# S3C_FrontpanelInterface.net
KiCad netlist of a schematic drawn in Altium Designer
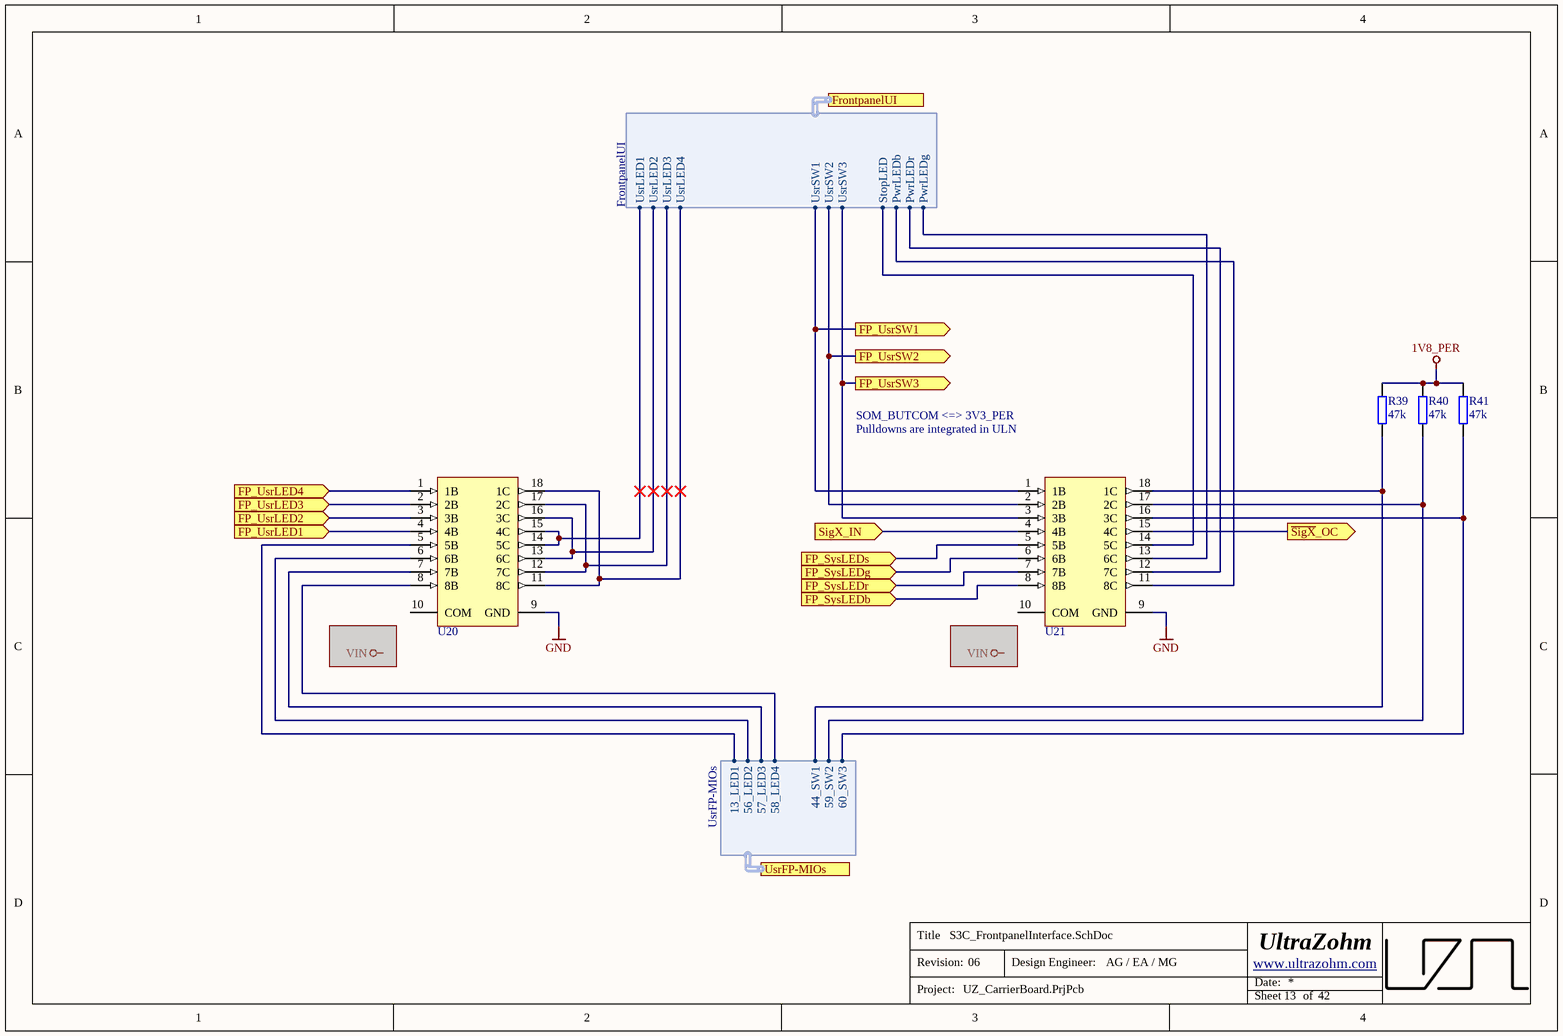
[diagram p0: S3C_FrontpanelInterface.SchDoc]

(export (version "E")
  (design (tool "Eeschema 10.0.6"))
  (components
    (comp (ref "R39")
      (value "47k")
      (footprint "R_0603_TE")
      (description "Generic resistor")
      (fields
        (field (name "MANUFACTURER PART NUMBER") "UZgen_R_0603_47k")
        (field (name "MANUFACTURER") "UZgen")
        (field (name "CREATED FROM") "UZgenTool")
      )
      (libsource (lib "user") (part "RES"))
    )
    (comp (ref "R40")
      (value "47k")
      (footprint "R_0603_TE")
      (description "Generic resistor")
      (fields
        (field (name "MANUFACTURER PART NUMBER") "UZgen_R_0603_47k")
        (field (name "MANUFACTURER") "UZgen")
        (field (name "CREATED FROM") "UZgenTool")
      )
      (libsource (lib "user") (part "RES"))
    )
    (comp (ref "R41")
      (value "47k")
      (footprint "R_0603_TE")
      (description "Generic resistor")
      (fields
        (field (name "MANUFACTURER PART NUMBER") "UZgen_R_0603_47k")
        (field (name "MANUFACTURER") "UZgen")
        (field (name "CREATED FROM") "UZgenTool")
      )
      (libsource (lib "user") (part "RES"))
    )
    (comp (ref "U20")
      (value "ULN2803A")
      (footprint "FP-SOICW-18LD-PL-1-IPC_B")
      (description "Darlington Transistors Eight NPN Array")
      (fields
        (field (name "MANUFACTURER") "UMW(Youtai Semiconductor Co., Ltd.)")
        (field (name "LCSC PART NUMBER") "C845537")
        (field (name "CREATED FROM") "FRosner")
      )
      (libsource (lib "user") (part "ULN2803"))
    )
    (comp (ref "U21")
      (value "ULN2803A")
      (footprint "FP-SOICW-18LD-PL-1-IPC_B")
      (description "Darlington Transistors Eight NPN Array")
      (fields
        (field (name "MANUFACTURER") "UMW(Youtai Semiconductor Co., Ltd.)")
        (field (name "LCSC PART NUMBER") "C845537")
        (field (name "CREATED FROM") "FRosner")
      )
      (libsource (lib "user") (part "ULN2803"))
    )
  )
  (nets
    (net (code "3") (name "/13_LED1") (class "Default")
      (node (ref "U20") (pin "5") (pinfunction "5B_5") (pintype "input"))
    )
    (net (code "4") (name "/44_SW1") (class "Default")
      (node (ref "R39") (pin "1") (pinfunction "1_1") (pintype "passive"))
      (node (ref "U21") (pin "18") (pinfunction "1C_18") (pintype "output"))
    )
    (net (code "5") (name "/56_LED2") (class "Default")
      (node (ref "U20") (pin "6") (pinfunction "6B_6") (pintype "input"))
    )
    (net (code "6") (name "/57_LED3") (class "Default")
      (node (ref "U20") (pin "7") (pinfunction "7B_7") (pintype "input"))
    )
    (net (code "7") (name "/58_LED4") (class "Default")
      (node (ref "U20") (pin "8") (pinfunction "8B_8") (pintype "input"))
    )
    (net (code "8") (name "/59_SW2") (class "Default")
      (node (ref "R40") (pin "1") (pinfunction "1_1") (pintype "passive"))
      (node (ref "U21") (pin "17") (pinfunction "2C_17") (pintype "output"))
    )
    (net (code "9") (name "/60_SW3") (class "Default")
      (node (ref "R41") (pin "1") (pinfunction "1_1") (pintype "passive"))
      (node (ref "U21") (pin "16") (pinfunction "3C_16") (pintype "output"))
    )
    (net (code "10") (name "/FP_SysLEDb") (class "Default")
      (node (ref "U21") (pin "8") (pinfunction "8B_8") (pintype "input"))
    )
    (net (code "11") (name "/FP_SysLEDg") (class "Default")
      (node (ref "U21") (pin "6") (pinfunction "6B_6") (pintype "input"))
    )
    (net (code "12") (name "/FP_SysLEDr") (class "Default")
      (node (ref "U21") (pin "7") (pinfunction "7B_7") (pintype "input"))
    )
    (net (code "13") (name "/FP_SysLEDs") (class "Default")
      (node (ref "U21") (pin "5") (pinfunction "5B_5") (pintype "input"))
    )
    (net (code "14") (name "/FP_UsrLED1") (class "Default")
      (node (ref "U20") (pin "4") (pinfunction "4B_4") (pintype "input"))
    )
    (net (code "15") (name "/FP_UsrLED2") (class "Default")
      (node (ref "U20") (pin "3") (pinfunction "3B_3") (pintype "input"))
    )
    (net (code "16") (name "/FP_UsrLED3") (class "Default")
      (node (ref "U20") (pin "2") (pinfunction "2B_2") (pintype "input"))
    )
    (net (code "17") (name "/FP_UsrLED4") (class "Default")
      (node (ref "U20") (pin "1") (pinfunction "1B_1") (pintype "input"))
    )
    (net (code "18") (name "/FP_UsrSW1") (class "Default")
      (node (ref "U21") (pin "1") (pinfunction "1B_1") (pintype "input"))
    )
    (net (code "19") (name "/FP_UsrSW2") (class "Default")
      (node (ref "U21") (pin "2") (pinfunction "2B_2") (pintype "input"))
    )
    (net (code "20") (name "/FP_UsrSW3") (class "Default")
      (node (ref "U21") (pin "3") (pinfunction "3B_3") (pintype "input"))
    )
    (net (code "21") (name "/PwrLEDb") (class "Default")
      (node (ref "U21") (pin "11") (pinfunction "8C_11") (pintype "output"))
    )
    (net (code "22") (name "/PwrLEDg") (class "Default")
      (node (ref "U21") (pin "13") (pinfunction "6C_13") (pintype "output"))
    )
    (net (code "23") (name "/PwrLEDr") (class "Default")
      (node (ref "U21") (pin "12") (pinfunction "7C_12") (pintype "output"))
    )
    (net (code "24") (name "/SigX_IN") (class "Default")
      (node (ref "U21") (pin "4") (pinfunction "4B_4") (pintype "input"))
    )
    (net (code "25") (name "/StopLED") (class "Default")
      (node (ref "U21") (pin "14") (pinfunction "5C_14") (pintype "output"))
    )
    (net (code "26") (name "/UsrLED1") (class "Default")
      (node (ref "U20") (pin "14") (pinfunction "5C_14") (pintype "output"))
      (node (ref "U20") (pin "15") (pinfunction "4C_15") (pintype "output"))
    )
    (net (code "27") (name "/UsrLED2") (class "Default")
      (node (ref "U20") (pin "13") (pinfunction "6C_13") (pintype "output"))
      (node (ref "U20") (pin "16") (pinfunction "3C_16") (pintype "output"))
    )
    (net (code "28") (name "/UsrLED3") (class "Default")
      (node (ref "U20") (pin "12") (pinfunction "7C_12") (pintype "output"))
      (node (ref "U20") (pin "17") (pinfunction "2C_17") (pintype "output"))
    )
    (net (code "29") (name "/UsrLED4") (class "Default")
      (node (ref "U20") (pin "11") (pinfunction "8C_11") (pintype "output"))
      (node (ref "U20") (pin "18") (pinfunction "1C_18") (pintype "output"))
    )
    (net (code "32") (name "/~{SigX}_OC") (class "Default")
      (node (ref "U21") (pin "15") (pinfunction "4C_15") (pintype "output"))
    )
    (net (code "33") (name "1V8_PER") (class "Default")
      (node (ref "R39") (pin "2") (pinfunction "2_2") (pintype "passive"))
      (node (ref "R40") (pin "2") (pinfunction "2_2") (pintype "passive"))
      (node (ref "R41") (pin "2") (pinfunction "2_2") (pintype "passive"))
    )
    (net (code "34") (name "GND") (class "Default")
      (node (ref "U20") (pin "9") (pinfunction "GND_9") (pintype "power_in"))
      (node (ref "U21") (pin "9") (pinfunction "GND_9") (pintype "power_in"))
    )
    (net (code "36") (name "unconnected-(U20-COM-Pad10)") (class "Default")
      (node (ref "U20") (pin "10") (pinfunction "COM_10") (pintype "passive"))
    )
    (net (code "37") (name "unconnected-(U21-COM-Pad10)") (class "Default")
      (node (ref "U21") (pin "10") (pinfunction "COM_10") (pintype "passive"))
    )
  )
)
